# CONNECTORS.net
KiCad netlist of a schematic drawn in Altium Designer
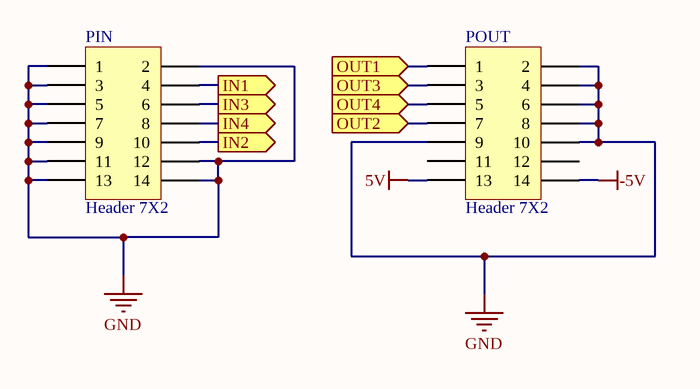
[diagram p0: CONNECTORS.SchDoc]

(export (version "E")
  (design (tool "Eeschema 10.0.6"))
  (components
    (comp (ref "PIN")
      (value "Header 7X2")
      (footprint "CONN_14x2_0.5IN")
      (description "Header, 7-Pin, Dual row")
      (fields (field (name "PUBLISHER") "Altium Limited"))
      (libsource (lib "Miscellaneous Connectors") (part "Header 7X2"))
    )
    (comp (ref "POUT")
      (value "Header 7X2")
      (footprint "CONN_14x2_0.5IN")
      (description "Header, 7-Pin, Dual row")
      (fields (field (name "PUBLISHER") "Altium Limited"))
      (libsource (lib "Miscellaneous Connectors") (part "Header 7X2"))
    )
  )
  (nets
    (net (code "1") (name "-5V") (class "Default")
      (node (ref "POUT") (pin "14") (pinfunction "14_14") (pintype "passive"))
    )
    (net (code "2") (name "/IN1") (class "Default")
      (node (ref "PIN") (pin "4") (pinfunction "4_4") (pintype "passive"))
    )
    (net (code "3") (name "/IN2") (class "Default")
      (node (ref "PIN") (pin "10") (pinfunction "10_10") (pintype "passive"))
    )
    (net (code "4") (name "/IN3") (class "Default")
      (node (ref "PIN") (pin "6") (pinfunction "6_6") (pintype "passive"))
    )
    (net (code "5") (name "/IN4") (class "Default")
      (node (ref "PIN") (pin "8") (pinfunction "8_8") (pintype "passive"))
    )
    (net (code "6") (name "/OUT1") (class "Default")
      (node (ref "POUT") (pin "1") (pinfunction "1_1") (pintype "passive"))
    )
    (net (code "7") (name "/OUT2") (class "Default")
      (node (ref "POUT") (pin "7") (pinfunction "7_7") (pintype "passive"))
    )
    (net (code "8") (name "/OUT3") (class "Default")
      (node (ref "POUT") (pin "3") (pinfunction "3_3") (pintype "passive"))
    )
    (net (code "9") (name "/OUT4") (class "Default")
      (node (ref "POUT") (pin "5") (pinfunction "5_5") (pintype "passive"))
    )
    (net (code "10") (name "5V") (class "Default")
      (node (ref "POUT") (pin "13") (pinfunction "13_13") (pintype "passive"))
    )
    (net (code "11") (name "GND") (class "Default")
      (node (ref "PIN") (pin "1") (pinfunction "1_1") (pintype "passive"))
      (node (ref "PIN") (pin "11") (pinfunction "11_11") (pintype "passive"))
      (node (ref "PIN") (pin "12") (pinfunction "12_12") (pintype "passive"))
      (node (ref "PIN") (pin "13") (pinfunction "13_13") (pintype "passive"))
      (node (ref "PIN") (pin "14") (pinfunction "14_14") (pintype "passive"))
      (node (ref "PIN") (pin "2") (pinfunction "2_2") (pintype "passive"))
      (node (ref "PIN") (pin "3") (pinfunction "3_3") (pintype "passive"))
      (node (ref "PIN") (pin "5") (pinfunction "5_5") (pintype "passive"))
      (node (ref "PIN") (pin "7") (pinfunction "7_7") (pintype "passive"))
      (node (ref "PIN") (pin "9") (pinfunction "9_9") (pintype "passive"))
      (node (ref "POUT") (pin "10") (pinfunction "10_10") (pintype "passive"))
      (node (ref "POUT") (pin "2") (pinfunction "2_2") (pintype "passive"))
      (node (ref "POUT") (pin "4") (pinfunction "4_4") (pintype "passive"))
      (node (ref "POUT") (pin "6") (pinfunction "6_6") (pintype "passive"))
      (node (ref "POUT") (pin "8") (pinfunction "8_8") (pintype "passive"))
      (node (ref "POUT") (pin "9") (pinfunction "9_9") (pintype "passive"))
    )
    (net (code "12") (name "unconnected-(POUT-Pad11)") (class "Default")
      (node (ref "POUT") (pin "11") (pinfunction "11_11") (pintype "passive"))
    )
    (net (code "13") (name "unconnected-(POUT-Pad12)") (class "Default")
      (node (ref "POUT") (pin "12") (pinfunction "12_12") (pintype "passive"))
    )
  )
)
